# AES50B.net
KiCad netlist of a schematic drawn in Altium Designer
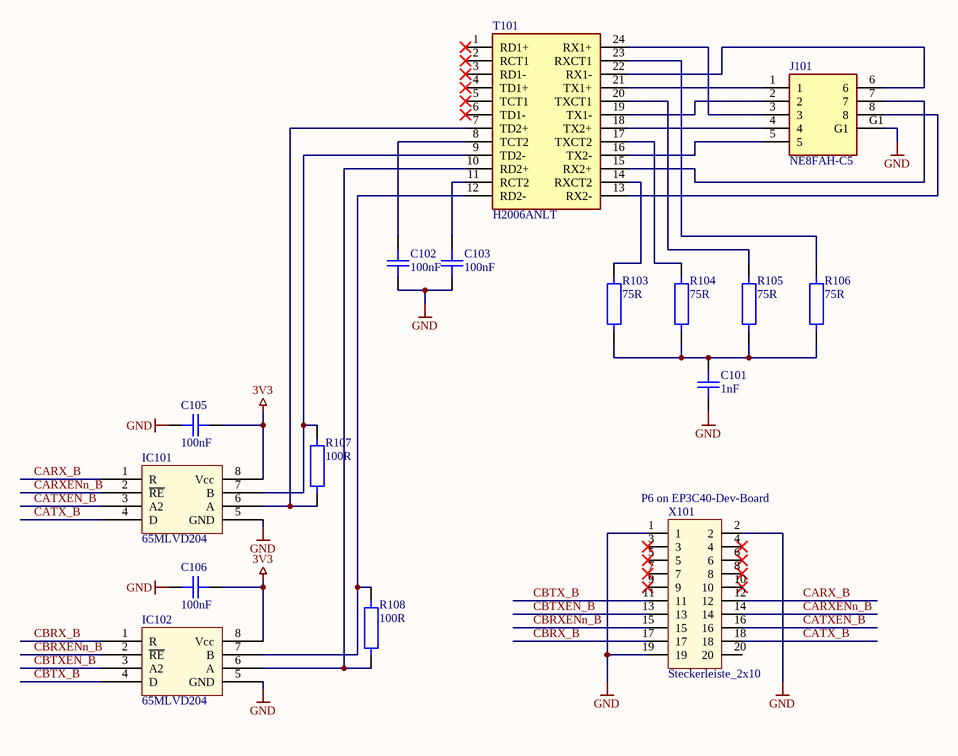
[diagram p0: AES50B.SchDoc]

(export (version "E")
  (design (tool "Eeschema 10.0.6"))
  (components
    (comp (ref "C101")
      (value "1nF")
      (footprint "1206")
      (description "1206_C")
      (libsource (lib "FPGA_Board_Library") (part "1206_C_1nF/63V"))
    )
    (comp (ref "C102")
      (value "100nF")
      (footprint "1206")
      (description "1206_C")
      (libsource (lib "FPGA_Board_Library") (part "1206_C_1nF/63V"))
    )
    (comp (ref "C103")
      (value "100nF")
      (footprint "1206")
      (description "1206_C")
      (libsource (lib "FPGA_Board_Library") (part "1206_C_1nF/63V"))
    )
    (comp (ref "C105")
      (value "100nF")
      (footprint "1206")
      (description "1206_C")
      (libsource (lib "FPGA_Board_Library") (part "1206_C_1nF/63V"))
    )
    (comp (ref "C106")
      (value "100nF")
      (footprint "1206")
      (description "1206_C")
      (libsource (lib "FPGA_Board_Library") (part "1206_C_1nF/63V"))
    )
    (comp (ref "IC101")
      (value "65MLVD204")
      (footprint "SOIC-8")
      (libsource (lib "AES50_Library") (part "65MLVD204"))
    )
    (comp (ref "IC102")
      (value "65MLVD204")
      (footprint "SOIC-8")
      (libsource (lib "AES50_Library") (part "65MLVD204"))
    )
    (comp (ref "J101")
      (value "NE8FAH-C5")
      (footprint "SamacSys:NE8FAHC5")
      (description "Connector")
      (fields (field (name "MOUSER PART NUMBER") "568-NE8FAH-C5"))
      (libsource (lib "*") (part "NE8FAH-C5"))
    )
    (comp (ref "R103")
      (value "75R")
      (footprint "1206")
      (description "1206_R")
      (libsource (lib "FPGA_Board_Library") (part "1206_R"))
    )
    (comp (ref "R104")
      (value "75R")
      (footprint "1206")
      (description "1206_R")
      (libsource (lib "FPGA_Board_Library") (part "1206_R"))
    )
    (comp (ref "R105")
      (value "75R")
      (footprint "1206")
      (description "1206_R")
      (libsource (lib "FPGA_Board_Library") (part "1206_R"))
    )
    (comp (ref "R106")
      (value "75R")
      (footprint "1206")
      (description "1206_R")
      (libsource (lib "FPGA_Board_Library") (part "1206_R"))
    )
    (comp (ref "R107")
      (value "100R")
      (footprint "1206")
      (description "1206_R")
      (libsource (lib "FPGA_Board_Library") (part "1206_R"))
    )
    (comp (ref "R108")
      (value "100R")
      (footprint "1206")
      (description "1206_R")
      (libsource (lib "FPGA_Board_Library") (part "1206_R"))
    )
    (comp (ref "T101")
      (value "H2006ANLT")
      (footprint "SamacSys:H2006ANLT")
      (description "Transformer")
      (fields (field (name "MOUSER PART NUMBER") "673-H2006ANLT"))
      (libsource (lib "*") (part "H2006ANLT"))
    )
    (comp (ref "X101")
      (value "Steckerleiste_2x10")
      (footprint "steckerleiste_2x10")
      (libsource (lib "FPGA_Board_Library") (part "Steckerleiste_2x10"))
    )
  )
  (nets
    (net (code "1") (name "/CARXENn_B") (class "Default")
      (node (ref "IC101") (pin "2") (pinfunction "~{RE}_2") (pintype "passive"))
      (node (ref "X101") (pin "14") (pinfunction "14_14") (pintype "passive"))
    )
    (net (code "2") (name "/CARX_B") (class "Default")
      (node (ref "IC101") (pin "1") (pinfunction "R_1") (pintype "passive"))
      (node (ref "X101") (pin "12") (pinfunction "12_12") (pintype "passive"))
    )
    (net (code "3") (name "/CATXEN_B") (class "Default")
      (node (ref "IC101") (pin "3") (pinfunction "A2_3") (pintype "passive"))
      (node (ref "X101") (pin "16") (pinfunction "16_16") (pintype "passive"))
    )
    (net (code "4") (name "/CATX_B") (class "Default")
      (node (ref "IC101") (pin "4") (pinfunction "D_4") (pintype "passive"))
      (node (ref "X101") (pin "18") (pinfunction "18_18") (pintype "passive"))
    )
    (net (code "5") (name "/CBRXENn_B") (class "Default")
      (node (ref "IC102") (pin "2") (pinfunction "~{RE}_2") (pintype "passive"))
      (node (ref "X101") (pin "15") (pinfunction "15_15") (pintype "passive"))
    )
    (net (code "6") (name "/CBRX_B") (class "Default")
      (node (ref "IC102") (pin "1") (pinfunction "R_1") (pintype "passive"))
      (node (ref "X101") (pin "17") (pinfunction "17_17") (pintype "passive"))
    )
    (net (code "7") (name "/CBTXEN_B") (class "Default")
      (node (ref "IC102") (pin "3") (pinfunction "A2_3") (pintype "passive"))
      (node (ref "X101") (pin "13") (pinfunction "13_13") (pintype "passive"))
    )
    (net (code "8") (name "/CBTX_B") (class "Default")
      (node (ref "IC102") (pin "4") (pinfunction "D_4") (pintype "passive"))
      (node (ref "X101") (pin "11") (pinfunction "11_11") (pintype "passive"))
    )
    (net (code "9") (name "3V3") (class "Default")
      (node (ref "C105") (pin "1") (pinfunction "1_1") (pintype "passive"))
      (node (ref "C106") (pin "1") (pinfunction "1_1") (pintype "passive"))
      (node (ref "IC101") (pin "8") (pinfunction "Vcc_8") (pintype "passive"))
      (node (ref "IC102") (pin "8") (pinfunction "Vcc_8") (pintype "passive"))
    )
    (net (code "10") (name "GND") (class "Default")
      (node (ref "C101") (pin "2") (pinfunction "2_2") (pintype "passive"))
      (node (ref "C102") (pin "2") (pinfunction "2_2") (pintype "passive"))
      (node (ref "C103") (pin "2") (pinfunction "2_2") (pintype "passive"))
      (node (ref "C105") (pin "2") (pinfunction "2_2") (pintype "passive"))
      (node (ref "C106") (pin "2") (pinfunction "2_2") (pintype "passive"))
      (node (ref "IC101") (pin "5") (pinfunction "GND_5") (pintype "passive"))
      (node (ref "IC102") (pin "5") (pinfunction "GND_5") (pintype "passive"))
      (node (ref "J101") (pin "G1") (pinfunction "G1_G1") (pintype "passive"))
      (node (ref "X101") (pin "1") (pinfunction "1_1") (pintype "passive"))
      (node (ref "X101") (pin "19") (pinfunction "19_19") (pintype "passive"))
      (node (ref "X101") (pin "2") (pinfunction "2_2") (pintype "passive"))
    )
    (net (code "11") (name "Net-(C101-Pad1)") (class "Default")
      (node (ref "C101") (pin "1") (pinfunction "1_1") (pintype "passive"))
      (node (ref "R103") (pin "1") (pinfunction "1_1") (pintype "passive"))
      (node (ref "R104") (pin "1") (pinfunction "1_1") (pintype "passive"))
      (node (ref "R105") (pin "1") (pinfunction "1_1") (pintype "passive"))
      (node (ref "R106") (pin "1") (pinfunction "1_1") (pintype "passive"))
    )
    (net (code "12") (name "Net-(IC101-A)") (class "Default")
      (node (ref "IC101") (pin "6") (pinfunction "A_6") (pintype "passive"))
      (node (ref "R107") (pin "1") (pinfunction "1_1") (pintype "passive"))
      (node (ref "T101") (pin "7") (pinfunction "TD2+_7") (pintype "passive"))
    )
    (net (code "13") (name "Net-(IC101-B)") (class "Default")
      (node (ref "IC101") (pin "7") (pinfunction "B_7") (pintype "passive"))
      (node (ref "R107") (pin "2") (pinfunction "2_2") (pintype "passive"))
      (node (ref "T101") (pin "9") (pinfunction "TD2-_9") (pintype "passive"))
    )
    (net (code "14") (name "Net-(IC102-A)") (class "Default")
      (node (ref "IC102") (pin "6") (pinfunction "A_6") (pintype "passive"))
      (node (ref "R108") (pin "1") (pinfunction "1_1") (pintype "passive"))
      (node (ref "T101") (pin "10") (pinfunction "RD2+_10") (pintype "passive"))
    )
    (net (code "15") (name "Net-(IC102-B)") (class "Default")
      (node (ref "IC102") (pin "7") (pinfunction "B_7") (pintype "passive"))
      (node (ref "R108") (pin "2") (pinfunction "2_2") (pintype "passive"))
      (node (ref "T101") (pin "12") (pinfunction "RD2-_12") (pintype "passive"))
    )
    (net (code "16") (name "Net-(T101-RCT2)") (class "Default")
      (node (ref "C103") (pin "1") (pinfunction "1_1") (pintype "passive"))
      (node (ref "T101") (pin "11") (pinfunction "RCT2_11") (pintype "passive"))
    )
    (net (code "17") (name "Net-(T101-RX1+)") (class "Default")
      (node (ref "J101") (pin "3") (pinfunction "3_3") (pintype "passive"))
      (node (ref "T101") (pin "24") (pinfunction "RX1+_24") (pintype "passive"))
    )
    (net (code "18") (name "Net-(T101-RX1-)") (class "Default")
      (node (ref "J101") (pin "6") (pinfunction "6_6") (pintype "passive"))
      (node (ref "T101") (pin "22") (pinfunction "RX1-_22") (pintype "passive"))
    )
    (net (code "19") (name "Net-(T101-RX2+)") (class "Default")
      (node (ref "J101") (pin "7") (pinfunction "7_7") (pintype "passive"))
      (node (ref "T101") (pin "15") (pinfunction "RX2+_15") (pintype "passive"))
    )
    (net (code "20") (name "Net-(T101-RX2-)") (class "Default")
      (node (ref "J101") (pin "8") (pinfunction "8_8") (pintype "passive"))
      (node (ref "T101") (pin "13") (pinfunction "RX2-_13") (pintype "passive"))
    )
    (net (code "21") (name "Net-(T101-RXCT1)") (class "Default")
      (node (ref "R106") (pin "2") (pinfunction "2_2") (pintype "passive"))
      (node (ref "T101") (pin "23") (pinfunction "RXCT1_23") (pintype "passive"))
    )
    (net (code "22") (name "Net-(T101-RXCT2)") (class "Default")
      (node (ref "R103") (pin "2") (pinfunction "2_2") (pintype "passive"))
      (node (ref "T101") (pin "14") (pinfunction "RXCT2_14") (pintype "passive"))
    )
    (net (code "23") (name "Net-(T101-TCT2)") (class "Default")
      (node (ref "C102") (pin "1") (pinfunction "1_1") (pintype "passive"))
      (node (ref "T101") (pin "8") (pinfunction "TCT2_8") (pintype "passive"))
    )
    (net (code "24") (name "Net-(T101-TX1+)") (class "Default")
      (node (ref "J101") (pin "1") (pinfunction "1_1") (pintype "passive"))
      (node (ref "T101") (pin "21") (pinfunction "TX1+_21") (pintype "passive"))
    )
    (net (code "25") (name "Net-(T101-TX1-)") (class "Default")
      (node (ref "J101") (pin "2") (pinfunction "2_2") (pintype "passive"))
      (node (ref "T101") (pin "19") (pinfunction "TX1-_19") (pintype "passive"))
    )
    (net (code "26") (name "Net-(T101-TX2+)") (class "Default")
      (node (ref "J101") (pin "4") (pinfunction "4_4") (pintype "passive"))
      (node (ref "T101") (pin "18") (pinfunction "TX2+_18") (pintype "passive"))
    )
    (net (code "27") (name "Net-(T101-TX2-)") (class "Default")
      (node (ref "J101") (pin "5") (pinfunction "5_5") (pintype "passive"))
      (node (ref "T101") (pin "16") (pinfunction "TX2-_16") (pintype "passive"))
    )
    (net (code "28") (name "Net-(T101-TXCT1)") (class "Default")
      (node (ref "R105") (pin "2") (pinfunction "2_2") (pintype "passive"))
      (node (ref "T101") (pin "20") (pinfunction "TXCT1_20") (pintype "passive"))
    )
    (net (code "29") (name "Net-(T101-TXCT2)") (class "Default")
      (node (ref "R104") (pin "2") (pinfunction "2_2") (pintype "passive"))
      (node (ref "T101") (pin "17") (pinfunction "TXCT2_17") (pintype "passive"))
    )
    (net (code "30") (name "unconnected-(T101-RCT1-Pad2)") (class "Default")
      (node (ref "T101") (pin "2") (pinfunction "RCT1_2") (pintype "passive+no_connect"))
    )
    (net (code "31") (name "unconnected-(T101-RD1+-Pad1)") (class "Default")
      (node (ref "T101") (pin "1") (pinfunction "RD1+_1") (pintype "passive+no_connect"))
    )
    (net (code "32") (name "unconnected-(T101-RD1--Pad3)") (class "Default")
      (node (ref "T101") (pin "3") (pinfunction "RD1-_3") (pintype "passive+no_connect"))
    )
    (net (code "33") (name "unconnected-(T101-TCT1-Pad5)") (class "Default")
      (node (ref "T101") (pin "5") (pinfunction "TCT1_5") (pintype "passive+no_connect"))
    )
    (net (code "34") (name "unconnected-(T101-TD1+-Pad4)") (class "Default")
      (node (ref "T101") (pin "4") (pinfunction "TD1+_4") (pintype "passive+no_connect"))
    )
    (net (code "35") (name "unconnected-(T101-TD1--Pad6)") (class "Default")
      (node (ref "T101") (pin "6") (pinfunction "TD1-_6") (pintype "passive+no_connect"))
    )
    (net (code "36") (name "unconnected-(X101-Pad3)") (class "Default")
      (node (ref "X101") (pin "3") (pinfunction "3_3") (pintype "passive+no_connect"))
    )
    (net (code "37") (name "unconnected-(X101-Pad4)") (class "Default")
      (node (ref "X101") (pin "4") (pinfunction "4_4") (pintype "passive+no_connect"))
    )
    (net (code "38") (name "unconnected-(X101-Pad5)") (class "Default")
      (node (ref "X101") (pin "5") (pinfunction "5_5") (pintype "passive+no_connect"))
    )
    (net (code "39") (name "unconnected-(X101-Pad6)") (class "Default")
      (node (ref "X101") (pin "6") (pinfunction "6_6") (pintype "passive+no_connect"))
    )
    (net (code "40") (name "unconnected-(X101-Pad7)") (class "Default")
      (node (ref "X101") (pin "7") (pinfunction "7_7") (pintype "passive+no_connect"))
    )
    (net (code "41") (name "unconnected-(X101-Pad8)") (class "Default")
      (node (ref "X101") (pin "8") (pinfunction "8_8") (pintype "passive+no_connect"))
    )
    (net (code "42") (name "unconnected-(X101-Pad9)") (class "Default")
      (node (ref "X101") (pin "9") (pinfunction "9_9") (pintype "passive+no_connect"))
    )
    (net (code "43") (name "unconnected-(X101-Pad10)") (class "Default")
      (node (ref "X101") (pin "10") (pinfunction "10_10") (pintype "passive+no_connect"))
    )
    (net (code "44") (name "unconnected-(X101-Pad20)") (class "Default")
      (node (ref "X101") (pin "20") (pinfunction "20_20") (pintype "passive"))
    )
  )
)
